# Ex_Adafruit_I2C_Adapter.net
KiCad netlist of a schematic drawn in EAGLE
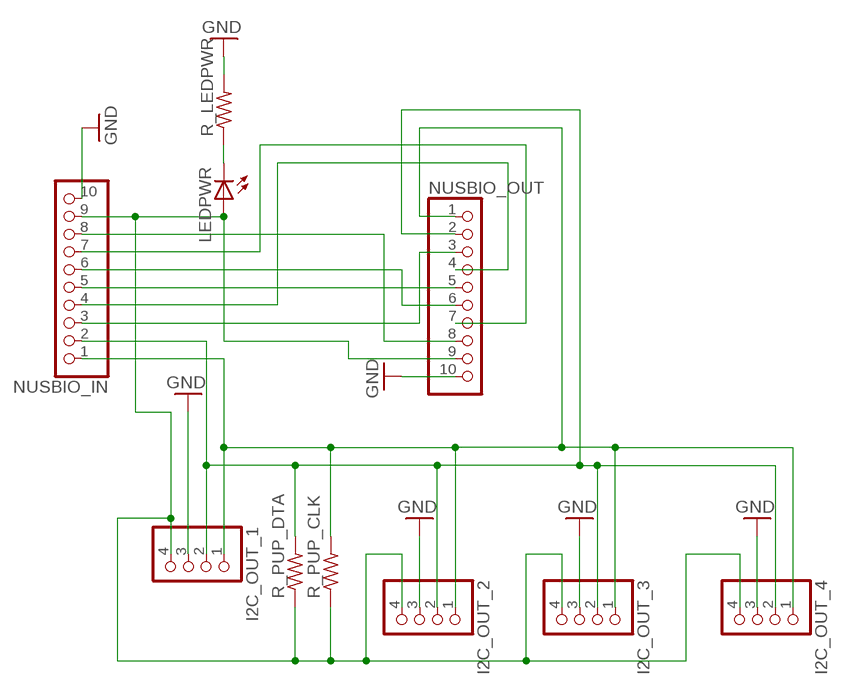
[diagram p0: schematic, sheet 1]

(export (version "E")
  (design (tool "Eeschema 10.0.6"))
  (components
    (comp (ref "I2C_OUT_1")
      (value "PINHD-1X4")
      (footprint "eagle-import:1X04")
      (libsource (lib "eagle-import") (part "PINHD-1X4"))
    )
    (comp (ref "I2C_OUT_2")
      (value "PINHD-1X4")
      (footprint "eagle-import:1X04")
      (libsource (lib "eagle-import") (part "PINHD-1X4"))
    )
    (comp (ref "I2C_OUT_3")
      (value "PINHD-1X4")
      (footprint "eagle-import:1X04")
      (libsource (lib "eagle-import") (part "PINHD-1X4"))
    )
    (comp (ref "I2C_OUT_4")
      (value "PINHD-1X4")
      (footprint "eagle-import:1X04")
      (libsource (lib "eagle-import") (part "PINHD-1X4"))
    )
    (comp (ref "LEDPWR")
      (value "LEDCHIPLED_0805")
      (footprint "eagle-import:CHIPLED_0805")
      (libsource (lib "eagle-import") (part "LEDCHIPLED_0805"))
    )
    (comp (ref "NUSBIO_IN")
      (value "PINHD-1X10")
      (footprint "eagle-import:1X10-BIG")
      (libsource (lib "eagle-import") (part "PINHD-1X10"))
    )
    (comp (ref "NUSBIO_OUT")
      (value "PINHD-1X10")
      (footprint "eagle-import:1X10-BIG")
      (libsource (lib "eagle-import") (part "PINHD-1X10"))
    )
    (comp (ref "R_LEDPWR")
      (value "R-US_R0805")
      (footprint "eagle-import:R0805")
      (libsource (lib "eagle-import") (part "R-US_R0805"))
    )
    (comp (ref "R_PUP_CLK")
      (value "R-US_R0805")
      (footprint "eagle-import:R0805")
      (libsource (lib "eagle-import") (part "R-US_R0805"))
    )
    (comp (ref "R_PUP_DTA")
      (value "R-US_R0805")
      (footprint "eagle-import:R0805")
      (libsource (lib "eagle-import") (part "R-US_R0805"))
    )
  )
  (nets
    (net (code "1") (name "GND") (class "Default")
      (node (ref "I2C_OUT_1") (pin "3") (pinfunction "3_3") (pintype "passive"))
      (node (ref "I2C_OUT_2") (pin "3") (pinfunction "3_3") (pintype "passive"))
      (node (ref "I2C_OUT_3") (pin "3") (pinfunction "3_3") (pintype "passive"))
      (node (ref "I2C_OUT_4") (pin "3") (pinfunction "3_3") (pintype "passive"))
      (node (ref "NUSBIO_IN") (pin "10") (pinfunction "10_10") (pintype "passive"))
      (node (ref "NUSBIO_OUT") (pin "10") (pinfunction "10_10") (pintype "passive"))
      (node (ref "R_LEDPWR") (pin "2") (pinfunction "2_2") (pintype "passive"))
    )
    (net (code "2") (name "Net-(I2C_OUT_1-Pad1)") (class "Default")
      (node (ref "I2C_OUT_1") (pin "1") (pinfunction "1_1") (pintype "passive"))
      (node (ref "I2C_OUT_2") (pin "1") (pinfunction "1_1") (pintype "passive"))
      (node (ref "I2C_OUT_3") (pin "1") (pinfunction "1_1") (pintype "passive"))
      (node (ref "I2C_OUT_4") (pin "1") (pinfunction "1_1") (pintype "passive"))
      (node (ref "NUSBIO_IN") (pin "1") (pinfunction "1_1") (pintype "passive"))
      (node (ref "NUSBIO_OUT") (pin "1") (pinfunction "1_1") (pintype "passive"))
      (node (ref "R_PUP_CLK") (pin "2") (pinfunction "2_2") (pintype "passive"))
    )
    (net (code "3") (name "Net-(I2C_OUT_1-Pad2)") (class "Default")
      (node (ref "I2C_OUT_1") (pin "2") (pinfunction "2_2") (pintype "passive"))
      (node (ref "I2C_OUT_2") (pin "2") (pinfunction "2_2") (pintype "passive"))
      (node (ref "I2C_OUT_3") (pin "2") (pinfunction "2_2") (pintype "passive"))
      (node (ref "I2C_OUT_4") (pin "2") (pinfunction "2_2") (pintype "passive"))
      (node (ref "NUSBIO_IN") (pin "2") (pinfunction "2_2") (pintype "passive"))
      (node (ref "NUSBIO_OUT") (pin "2") (pinfunction "2_2") (pintype "passive"))
      (node (ref "R_PUP_DTA") (pin "2") (pinfunction "2_2") (pintype "passive"))
    )
    (net (code "4") (name "Net-(I2C_OUT_1-Pad4)") (class "Default")
      (node (ref "I2C_OUT_1") (pin "4") (pinfunction "4_4") (pintype "passive"))
      (node (ref "I2C_OUT_2") (pin "4") (pinfunction "4_4") (pintype "passive"))
      (node (ref "I2C_OUT_3") (pin "4") (pinfunction "4_4") (pintype "passive"))
      (node (ref "I2C_OUT_4") (pin "4") (pinfunction "4_4") (pintype "passive"))
      (node (ref "LEDPWR") (pin "A") (pinfunction "A_A") (pintype "passive"))
      (node (ref "NUSBIO_IN") (pin "9") (pinfunction "9_9") (pintype "passive"))
      (node (ref "NUSBIO_OUT") (pin "9") (pinfunction "9_9") (pintype "passive"))
      (node (ref "R_PUP_CLK") (pin "1") (pinfunction "1_1") (pintype "passive"))
      (node (ref "R_PUP_DTA") (pin "1") (pinfunction "1_1") (pintype "passive"))
    )
    (net (code "5") (name "Net-(LEDPWR-PadC)") (class "Default")
      (node (ref "LEDPWR") (pin "C") (pinfunction "C_C") (pintype "passive"))
      (node (ref "R_LEDPWR") (pin "1") (pinfunction "1_1") (pintype "passive"))
    )
    (net (code "6") (name "Net-(NUSBIO_IN-Pad3)") (class "Default")
      (node (ref "NUSBIO_IN") (pin "3") (pinfunction "3_3") (pintype "passive"))
      (node (ref "NUSBIO_OUT") (pin "3") (pinfunction "3_3") (pintype "passive"))
    )
    (net (code "7") (name "Net-(NUSBIO_IN-Pad4)") (class "Default")
      (node (ref "NUSBIO_IN") (pin "4") (pinfunction "4_4") (pintype "passive"))
      (node (ref "NUSBIO_OUT") (pin "4") (pinfunction "4_4") (pintype "passive"))
    )
    (net (code "8") (name "Net-(NUSBIO_IN-Pad5)") (class "Default")
      (node (ref "NUSBIO_IN") (pin "5") (pinfunction "5_5") (pintype "passive"))
      (node (ref "NUSBIO_OUT") (pin "5") (pinfunction "5_5") (pintype "passive"))
    )
    (net (code "9") (name "Net-(NUSBIO_IN-Pad6)") (class "Default")
      (node (ref "NUSBIO_IN") (pin "6") (pinfunction "6_6") (pintype "passive"))
      (node (ref "NUSBIO_OUT") (pin "6") (pinfunction "6_6") (pintype "passive"))
    )
    (net (code "10") (name "Net-(NUSBIO_IN-Pad7)") (class "Default")
      (node (ref "NUSBIO_IN") (pin "7") (pinfunction "7_7") (pintype "passive"))
      (node (ref "NUSBIO_OUT") (pin "7") (pinfunction "7_7") (pintype "passive"))
    )
    (net (code "11") (name "Net-(NUSBIO_IN-Pad8)") (class "Default")
      (node (ref "NUSBIO_IN") (pin "8") (pinfunction "8_8") (pintype "passive"))
      (node (ref "NUSBIO_OUT") (pin "8") (pinfunction "8_8") (pintype "passive"))
    )
  )
)
